# RGB_to_PAL_Encoder.net
KiCad netlist of a schematic drawn in Altium Designer
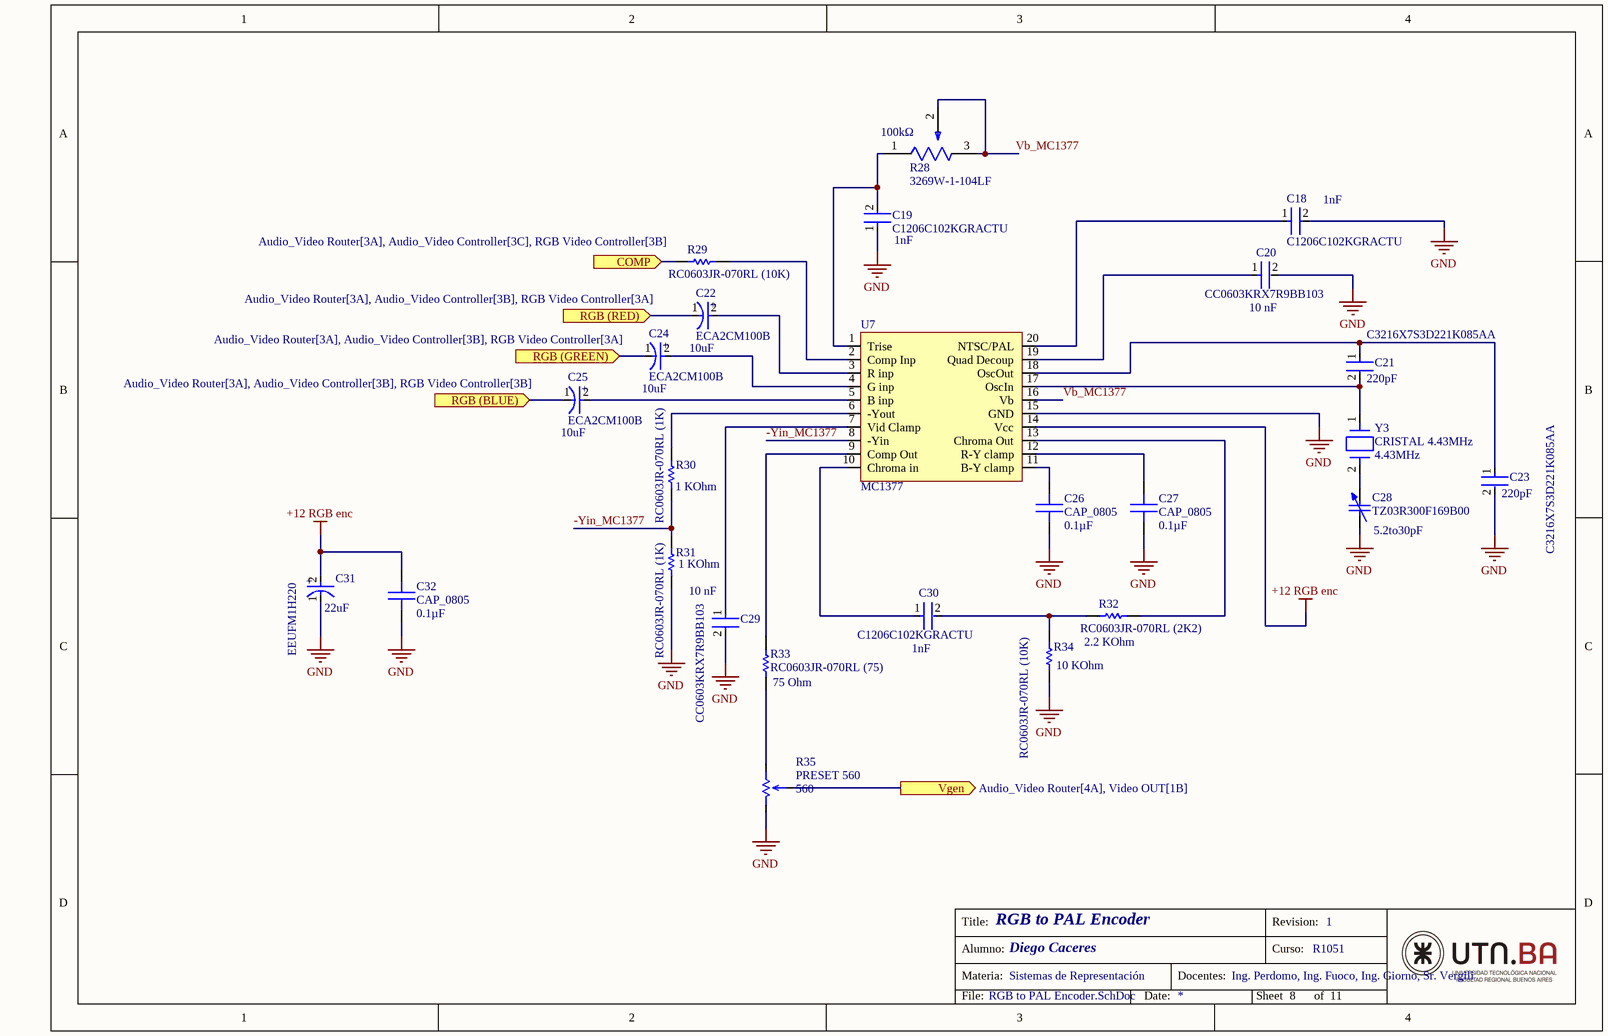
[diagram p0: RGB to PAL Encoder.SchDoc]

(export (version "E")
  (design (tool "Eeschema 10.0.6"))
  (components
    (comp (ref "C18")
      (value "C1206C102KGRACTU")
      (footprint "FP-C1206C-EF-MFG")
      (description "CAP CER 1000PF 2KV X7R 1206")
      (fields
        (field (name "VOLTAGE") "2kV")
        (field (name "TOLERANCE") "10%")
        (field (name "CAPACITANCE") "1nF")
      )
      (libsource (lib "Altium Content Vault") (part "b4654b650e69147ec39a6b967a45e02"))
    )
    (comp (ref "C19")
      (value "C1206C102KGRACTU")
      (footprint "FP-C1206C-EF-MFG")
      (description "CAP CER 1000PF 2KV X7R 1206")
      (fields
        (field (name "VOLTAGE") "2kV")
        (field (name "TOLERANCE") "10%")
        (field (name "CAPACITANCE") "1nF")
      )
      (libsource (lib "Altium Content Vault") (part "b4654b650e69147ec39a6b967a45e02"))
    )
    (comp (ref "C20")
      (value "CC0603KRX7R9BB103")
      (footprint "FP-CC0603-DA-MFG")
      (description "CAP CER 10000PF 50V X7R 0603")
      (fields
        (field (name "TOLERANCE") "0.1")
        (field (name "MANUFACTURER") "YAGEO")
        (field (name "CAPACITANCE") "10 nF")
      )
      (libsource (lib "Altium Content Vault") (part "11868f565c42a9108669ba33697ecf6"))
    )
    (comp (ref "C21")
      (value "C3216X7S3D221K085AA")
      (footprint "FP-C3216-085-0_2-MFG")
      (description "Multilayer Ceramic Capacitors 220pF ±10% 2000V X7S SMD 1206")
      (fields (field (name "CAPACITANCE") "220pF") (field (name "TOLERANCE") "10%"))
      (libsource (lib "Altium Content Vault") (part "11868f565c42a9108669ba33697ecf6"))
    )
    (comp (ref "C22")
      (value "ECA2CM100B")
      (footprint "FP-RAD-TH-D_10_0_5-L_12_5-MFG")
      (description "Aluminum Electrolytic Capacitors (Radial Lead Type) 10uF ±20% 160V")
      (fields (field (name "TOLERANCE") "20%") (field (name "CAPACITANCE") "10uF"))
      (libsource (lib "Altium Content Vault") (part "203bc49f2ac43e59fd269a8c329ed05"))
    )
    (comp (ref "C23")
      (value "C3216X7S3D221K085AA")
      (footprint "FP-C3216-085-0_2-MFG")
      (description "Multilayer Ceramic Capacitors 220pF ±10% 2000V X7S SMD 1206")
      (fields (field (name "CAPACITANCE") "220pF") (field (name "TOLERANCE") "10%"))
      (libsource (lib "Altium Content Vault") (part "11868f565c42a9108669ba33697ecf6"))
    )
    (comp (ref "C24")
      (value "ECA2CM100B")
      (footprint "FP-RAD-TH-D_10_0_5-L_12_5-MFG")
      (description "Aluminum Electrolytic Capacitors (Radial Lead Type) 10uF ±20% 160V")
      (fields (field (name "TOLERANCE") "20%") (field (name "CAPACITANCE") "10uF"))
      (libsource (lib "Altium Content Vault") (part "203bc49f2ac43e59fd269a8c329ed05"))
    )
    (comp (ref "C25")
      (value "ECA2CM100B")
      (footprint "FP-RAD-TH-D_10_0_5-L_12_5-MFG")
      (description "Aluminum Electrolytic Capacitors (Radial Lead Type) 10uF ±20% 160V")
      (fields (field (name "TOLERANCE") "20%") (field (name "CAPACITANCE") "10uF"))
      (libsource (lib "Altium Content Vault") (part "203bc49f2ac43e59fd269a8c329ed05"))
    )
    (comp (ref "C26")
      (value "CAP_0805")
      (footprint "0805_CAPACITOR_DCACERES")
      (description "Capacitor SMD, encapsulado 0805")
      (fields (field (name "ALTIUM_VALUE") "0.1µF"))
      (libsource (lib "PF_Schlib") (part "CAPACITOR_0805_Caceres"))
    )
    (comp (ref "C27")
      (value "CAP_0805")
      (footprint "0805_CAPACITOR_DCACERES")
      (description "Capacitor SMD, encapsulado 0805")
      (fields (field (name "ALTIUM_VALUE") "0.1µF"))
      (libsource (lib "PF_Schlib") (part "CAPACITOR_0805_Caceres"))
    )
    (comp (ref "C28")
      (value "TZ03R300F169B00")
      (footprint "MURA-TZ03-2_V")
      (description "Variable Capacitor, Miniature Ceramic Trimmer, Green, 30 pF, -25 to 85 degC, 2-Pin THD, Bulk")
      (fields (field (name "MANUFACTURER") "Murata") (field (name "CAPACITANCE") "5.2to30pF"))
      (libsource (lib "Altium Content Vault") (part "CAP-VAR-2"))
    )
    (comp (ref "C29")
      (value "CC0603KRX7R9BB103")
      (footprint "FP-CC0603-DA-MFG")
      (description "CAP CER 10000PF 50V X7R 0603")
      (fields
        (field (name "TOLERANCE") "0.1")
        (field (name "MANUFACTURER") "YAGEO")
        (field (name "ALTIUM_VALUE") "10 nF")
      )
      (libsource (lib "Altium Content Vault") (part "11868f565c42a9108669ba33697ecf6"))
    )
    (comp (ref "C30")
      (value "C1206C102KGRACTU")
      (footprint "FP-C1206C-EF-MFG")
      (description "CAP CER 1000PF 2KV X7R 1206")
      (fields
        (field (name "VOLTAGE") "2kV")
        (field (name "TOLERANCE") "10%")
        (field (name "CAPACITANCE") "1nF")
      )
      (libsource (lib "Altium Content Vault") (part "b4654b650e69147ec39a6b967a45e02"))
    )
    (comp (ref "C31")
      (value "EEUFM1H220")
      (footprint "FP-RAD-TH-D_5_0_5-L_11_1-MFG")
      (description "Aluminum Electrolytic Capacitors (Radial Lead Type) 22uF ±20% 50V")
      (fields
        (field (name "TOLERANCE") "20%")
        (field (name "VOLTAGE") "50V")
        (field (name "CAPACITANCE") "22uF")
      )
      (libsource (lib "Altium Content Vault") (part "a00bbbee19879c290e62620ae7e47b1"))
    )
    (comp (ref "C32")
      (value "CAP_0805")
      (footprint "0805_CAPACITOR_DCACERES")
      (description "Capacitor SMD, encapsulado 0805")
      (fields (field (name "ALTIUM_VALUE") "0.1µF"))
      (libsource (lib "PF_Schlib") (part "CAPACITOR_0805_Caceres"))
    )
    (comp (ref "R28")
      (value "3269W-1-104LF")
      (footprint "FP-3269W-MFG")
      (description "TRIMMER 100K OHM 0.25W SMD")
      (fields
        (field (name "MANUFACTURER") "Bourns")
        (field (name "TOLERANCE") "10%")
        (field (name "RESISTANCE") "100kΩ")
      )
      (libsource (lib "Altium Content Vault") (part "e2bd51d327feade59aab0772042b0d4"))
    )
    (comp (ref "R29")
      (value "RC0603JR-070RL (10K)")
      (footprint "RESC1608X55X25ML10T15")
      (description "Chip Resistor, 0 Ohm, +/- 5%, 0.1 W, -55 to 155 degC, 0603 (1608 Metric), RoHS, Tape and Reel")
      (fields (field (name "TOLERANCE") "5%") (field (name "MANUFACTURER") "Yageo"))
      (libsource (lib "Altium Content Vault") (part "RES-2"))
    )
    (comp (ref "R30")
      (value "RC0603JR-070RL (1K)")
      (footprint "RESC1608X55X25ML10T15")
      (description "Chip Resistor, 0 Ohm, +/- 5%, 0.1 W, -55 to 155 degC, 0603 (1608 Metric), RoHS, Tape and Reel")
      (fields
        (field (name "TOLERANCE") "5%")
        (field (name "RESISTANCE") "1 KOhm")
        (field (name "MANUFACTURER") "Yageo")
      )
      (libsource (lib "Altium Content Vault") (part "RES-2"))
    )
    (comp (ref "R31")
      (value "RC0603JR-070RL (1K)")
      (footprint "RESC1608X55X25ML10T15")
      (description "Chip Resistor, 0 Ohm, +/- 5%, 0.1 W, -55 to 155 degC, 0603 (1608 Metric), RoHS, Tape and Reel")
      (fields
        (field (name "TOLERANCE") "5%")
        (field (name "RESISTANCE") "1 KOhm")
        (field (name "MANUFACTURER") "Yageo")
      )
      (libsource (lib "Altium Content Vault") (part "RES-2"))
    )
    (comp (ref "R32")
      (value "RC0603JR-070RL (2K2)")
      (footprint "RESC1608X55X25ML10T15")
      (description "Chip Resistor, 0 Ohm, +/- 5%, 0.1 W, -55 to 155 degC, 0603 (1608 Metric), RoHS, Tape and Reel")
      (fields
        (field (name "TOLERANCE") "5%")
        (field (name "RESISTANCE") "2.2 KOhm")
        (field (name "MANUFACTURER") "Yageo")
      )
      (libsource (lib "Altium Content Vault") (part "RES-2"))
    )
    (comp (ref "R33")
      (value "RC0603JR-070RL (75)")
      (footprint "RESC1608X55X25ML10T15")
      (description "Chip Resistor, 0 Ohm, +/- 5%, 0.1 W, -55 to 155 degC, 0603 (1608 Metric), RoHS, Tape and Reel")
      (fields
        (field (name "TOLERANCE") "5%")
        (field (name "RESISTANCE") "75 Ohm")
        (field (name "MANUFACTURER") "Yageo")
      )
      (libsource (lib "Altium Content Vault") (part "RES-2"))
    )
    (comp (ref "R34")
      (value "RC0603JR-070RL (10K)")
      (footprint "RESC1608X55X25ML10T15")
      (description "Chip Resistor, 0 Ohm, +/- 5%, 0.1 W, -55 to 155 degC, 0603 (1608 Metric), RoHS, Tape and Reel")
      (fields
        (field (name "TOLERANCE") "5%")
        (field (name "RESISTANCE") "10 KOhm")
        (field (name "MANUFACTURER") "Yageo")
      )
      (libsource (lib "Altium Content Vault") (part "RES-2"))
    )
    (comp (ref "R35")
      (value "PRESET 560")
      (footprint "3386P_PRESET_560_DCaceres")
      (description "Preset 560, Thru Hole\r\nManufacturer Part Search 3386P-1-472LF")
      (fields (field (name "PARTNUMBER") "3386P-1-472LF") (field (name "ALTIUM_VALUE") "560"))
      (libsource (lib "PF_Schlib") (part "Preset_560_Caceres"))
    )
    (comp (ref "U7")
      (value "MC1377")
      (footprint "CASE 738-03_ISSUE E_MC1377_DCACERES")
      (description "MC1377, Thru Hole")
      (fields (field (name "PARTNUMBER") "MC1377P") (field (name "MANUFACTURER") "Motorola"))
      (libsource (lib "PF_Schlib") (part "MC1377_Caceres"))
    )
    (comp (ref "Y3")
      (value "CRISTAL 4.43MHz")
      (footprint "HC-49/US_SMD_CRISTAL 4.43MHz_DCACERES")
      (description "Cristal SMD 4.43MHz")
      (fields
        (field (name "FREQUENCY") "4.43MHz")
        (field (name "PARTNUMBER") "ABLS-4.433619MHZ-B4-T")
        (field (name "MANUFACTURER") "Abracon")
      )
      (libsource (lib "PF_Schlib") (part "Cristal_4.43MHz_Caceres"))
    )
  )
  (nets
    (net (code "1") (name "+12 RGB enc") (class "Default")
      (node (ref "C31") (pin "2") (pinfunction "A_2") (pintype "passive"))
      (node (ref "C32") (pin "2") (pinfunction "2_2") (pintype "passive"))
      (node (ref "U7") (pin "14") (pinfunction "Vcc_14") (pintype "passive"))
    )
    (net (code "2") (name "/-Yin_MC1377") (class "Default")
      (node (ref "R30") (pin "2") (pinfunction "2_2") (pintype "passive"))
      (node (ref "R31") (pin "1") (pinfunction "1_1") (pintype "passive"))
      (node (ref "U7") (pin "8") (pinfunction "-Yin_8") (pintype "passive"))
    )
    (net (code "3") (name "/COMP") (class "Default")
      (node (ref "R29") (pin "2") (pinfunction "2_2") (pintype "passive"))
    )
    (net (code "4") (name "/RGB (BLUE)") (class "Default")
      (node (ref "C25") (pin "1") (pinfunction "C_1") (pintype "passive"))
    )
    (net (code "5") (name "/RGB (GREEN)") (class "Default")
      (node (ref "C24") (pin "1") (pinfunction "C_1") (pintype "passive"))
    )
    (net (code "6") (name "/RGB (RED)") (class "Default")
      (node (ref "C22") (pin "1") (pinfunction "C_1") (pintype "passive"))
    )
    (net (code "7") (name "/Vb_MC1377") (class "Default")
      (node (ref "R28") (pin "2") (pinfunction "WIPER_2") (pintype "passive"))
      (node (ref "R28") (pin "3") (pinfunction "CW_3") (pintype "passive"))
      (node (ref "U7") (pin "16") (pinfunction "Vb_16") (pintype "passive"))
    )
    (net (code "8") (name "/Vgen") (class "Default")
      (node (ref "R35") (pin "3") (pinfunction "3_3") (pintype "passive"))
    )
    (net (code "9") (name "GND") (class "Default")
      (node (ref "C18") (pin "2") (pinfunction "2_2") (pintype "passive"))
      (node (ref "C19") (pin "1") (pinfunction "1_1") (pintype "passive"))
      (node (ref "C20") (pin "2") (pinfunction "2_2") (pintype "passive"))
      (node (ref "C23") (pin "2") (pinfunction "2_2") (pintype "passive"))
      (node (ref "C26") (pin "1") (pinfunction "1_1") (pintype "passive"))
      (node (ref "C27") (pin "1") (pinfunction "1_1") (pintype "passive"))
      (node (ref "C28") (pin "1") (pinfunction "1_1") (pintype "passive"))
      (node (ref "C29") (pin "2") (pinfunction "2_2") (pintype "passive"))
      (node (ref "C31") (pin "1") (pinfunction "C_1") (pintype "passive"))
      (node (ref "C32") (pin "1") (pinfunction "1_1") (pintype "passive"))
      (node (ref "R31") (pin "2") (pinfunction "2_2") (pintype "passive"))
      (node (ref "R34") (pin "2") (pinfunction "2_2") (pintype "passive"))
      (node (ref "R35") (pin "1") (pinfunction "1_1") (pintype "passive"))
      (node (ref "U7") (pin "15") (pinfunction "GND_15") (pintype "passive"))
    )
    (net (code "10") (name "Net-(C22-A)") (class "Default")
      (node (ref "C22") (pin "2") (pinfunction "A_2") (pintype "passive"))
      (node (ref "U7") (pin "3") (pinfunction "R_inp_3") (pintype "passive"))
    )
    (net (code "11") (name "Net-(C24-A)") (class "Default")
      (node (ref "C24") (pin "2") (pinfunction "A_2") (pintype "passive"))
      (node (ref "U7") (pin "4") (pinfunction "G_inp_4") (pintype "passive"))
    )
    (net (code "12") (name "Net-(C25-A)") (class "Default")
      (node (ref "C25") (pin "2") (pinfunction "A_2") (pintype "passive"))
      (node (ref "U7") (pin "5") (pinfunction "B_inp_5") (pintype "passive"))
    )
    (net (code "13") (name "Net-(C28-Pad2)") (class "Default")
      (node (ref "C28") (pin "2") (pinfunction "2_2") (pintype "passive"))
      (node (ref "Y3") (pin "2") (pinfunction "2_2") (pintype "passive"))
    )
    (net (code "14") (name "Net-(C30-Pad2)") (class "Default")
      (node (ref "C30") (pin "2") (pinfunction "2_2") (pintype "passive"))
      (node (ref "R32") (pin "2") (pinfunction "2_2") (pintype "passive"))
      (node (ref "R34") (pin "1") (pinfunction "1_1") (pintype "passive"))
    )
    (net (code "15") (name "Net-(R28-CCW)") (class "Default")
      (node (ref "C19") (pin "2") (pinfunction "2_2") (pintype "passive"))
      (node (ref "R28") (pin "1") (pinfunction "CCW_1") (pintype "passive"))
      (node (ref "U7") (pin "1") (pinfunction "Trise_1") (pintype "passive"))
    )
    (net (code "16") (name "Net-(R33-Pad1)") (class "Default")
      (node (ref "R33") (pin "1") (pinfunction "1_1") (pintype "passive"))
      (node (ref "R35") (pin "2") (pinfunction "1_2") (pintype "passive"))
    )
    (net (code "17") (name "Net-(U7--Yout)") (class "Default")
      (node (ref "R30") (pin "1") (pinfunction "1_1") (pintype "passive"))
      (node (ref "U7") (pin "6") (pinfunction "-Yout_6") (pintype "passive"))
    )
    (net (code "18") (name "Net-(U7-B-Y_clamp)") (class "Default")
      (node (ref "C26") (pin "2") (pinfunction "2_2") (pintype "passive"))
      (node (ref "U7") (pin "11") (pinfunction "B-Y_clamp_11") (pintype "passive"))
    )
    (net (code "19") (name "Net-(U7-Chroma_Out)") (class "Default")
      (node (ref "R32") (pin "1") (pinfunction "1_1") (pintype "passive"))
      (node (ref "U7") (pin "13") (pinfunction "Chroma_Out_13") (pintype "passive"))
    )
    (net (code "20") (name "Net-(U7-Chroma_in)") (class "Default")
      (node (ref "C30") (pin "1") (pinfunction "1_1") (pintype "passive"))
      (node (ref "U7") (pin "10") (pinfunction "Chroma_in_10") (pintype "passive"))
    )
    (net (code "21") (name "Net-(U7-Comp_Inp)") (class "Default")
      (node (ref "R29") (pin "1") (pinfunction "1_1") (pintype "passive"))
      (node (ref "U7") (pin "2") (pinfunction "Comp_Inp_2") (pintype "passive"))
    )
    (net (code "22") (name "Net-(U7-Comp_Out)") (class "Default")
      (node (ref "R33") (pin "2") (pinfunction "2_2") (pintype "passive"))
      (node (ref "U7") (pin "9") (pinfunction "Comp_Out_9") (pintype "passive"))
    )
    (net (code "23") (name "Net-(U7-NTSC{slash}PAL)") (class "Default")
      (node (ref "C18") (pin "1") (pinfunction "1_1") (pintype "passive"))
      (node (ref "U7") (pin "20") (pinfunction "NTSC/PAL_20") (pintype "passive"))
    )
    (net (code "24") (name "Net-(U7-OscIn)") (class "Default")
      (node (ref "C21") (pin "2") (pinfunction "2_2") (pintype "passive"))
      (node (ref "U7") (pin "17") (pinfunction "OscIn_17") (pintype "passive"))
      (node (ref "Y3") (pin "1") (pinfunction "1_1") (pintype "passive"))
    )
    (net (code "25") (name "Net-(U7-OscOut)") (class "Default")
      (node (ref "C21") (pin "1") (pinfunction "1_1") (pintype "passive"))
      (node (ref "C23") (pin "1") (pinfunction "1_1") (pintype "passive"))
      (node (ref "U7") (pin "18") (pinfunction "OscOut_18") (pintype "passive"))
    )
    (net (code "26") (name "Net-(U7-Quad_Decoup)") (class "Default")
      (node (ref "C20") (pin "1") (pinfunction "1_1") (pintype "passive"))
      (node (ref "U7") (pin "19") (pinfunction "Quad_Decoup_19") (pintype "passive"))
    )
    (net (code "27") (name "Net-(U7-R-Y_clamp)") (class "Default")
      (node (ref "C27") (pin "2") (pinfunction "2_2") (pintype "passive"))
      (node (ref "U7") (pin "12") (pinfunction "R-Y_clamp_12") (pintype "passive"))
    )
    (net (code "28") (name "Net-(U7-Vid_Clamp)") (class "Default")
      (node (ref "C29") (pin "1") (pinfunction "1_1") (pintype "passive"))
      (node (ref "U7") (pin "7") (pinfunction "Vid_Clamp_7") (pintype "passive"))
    )
  )
)
